# IronDriverInterfaceRevA.net
KiCad netlist of a schematic drawn in EAGLE
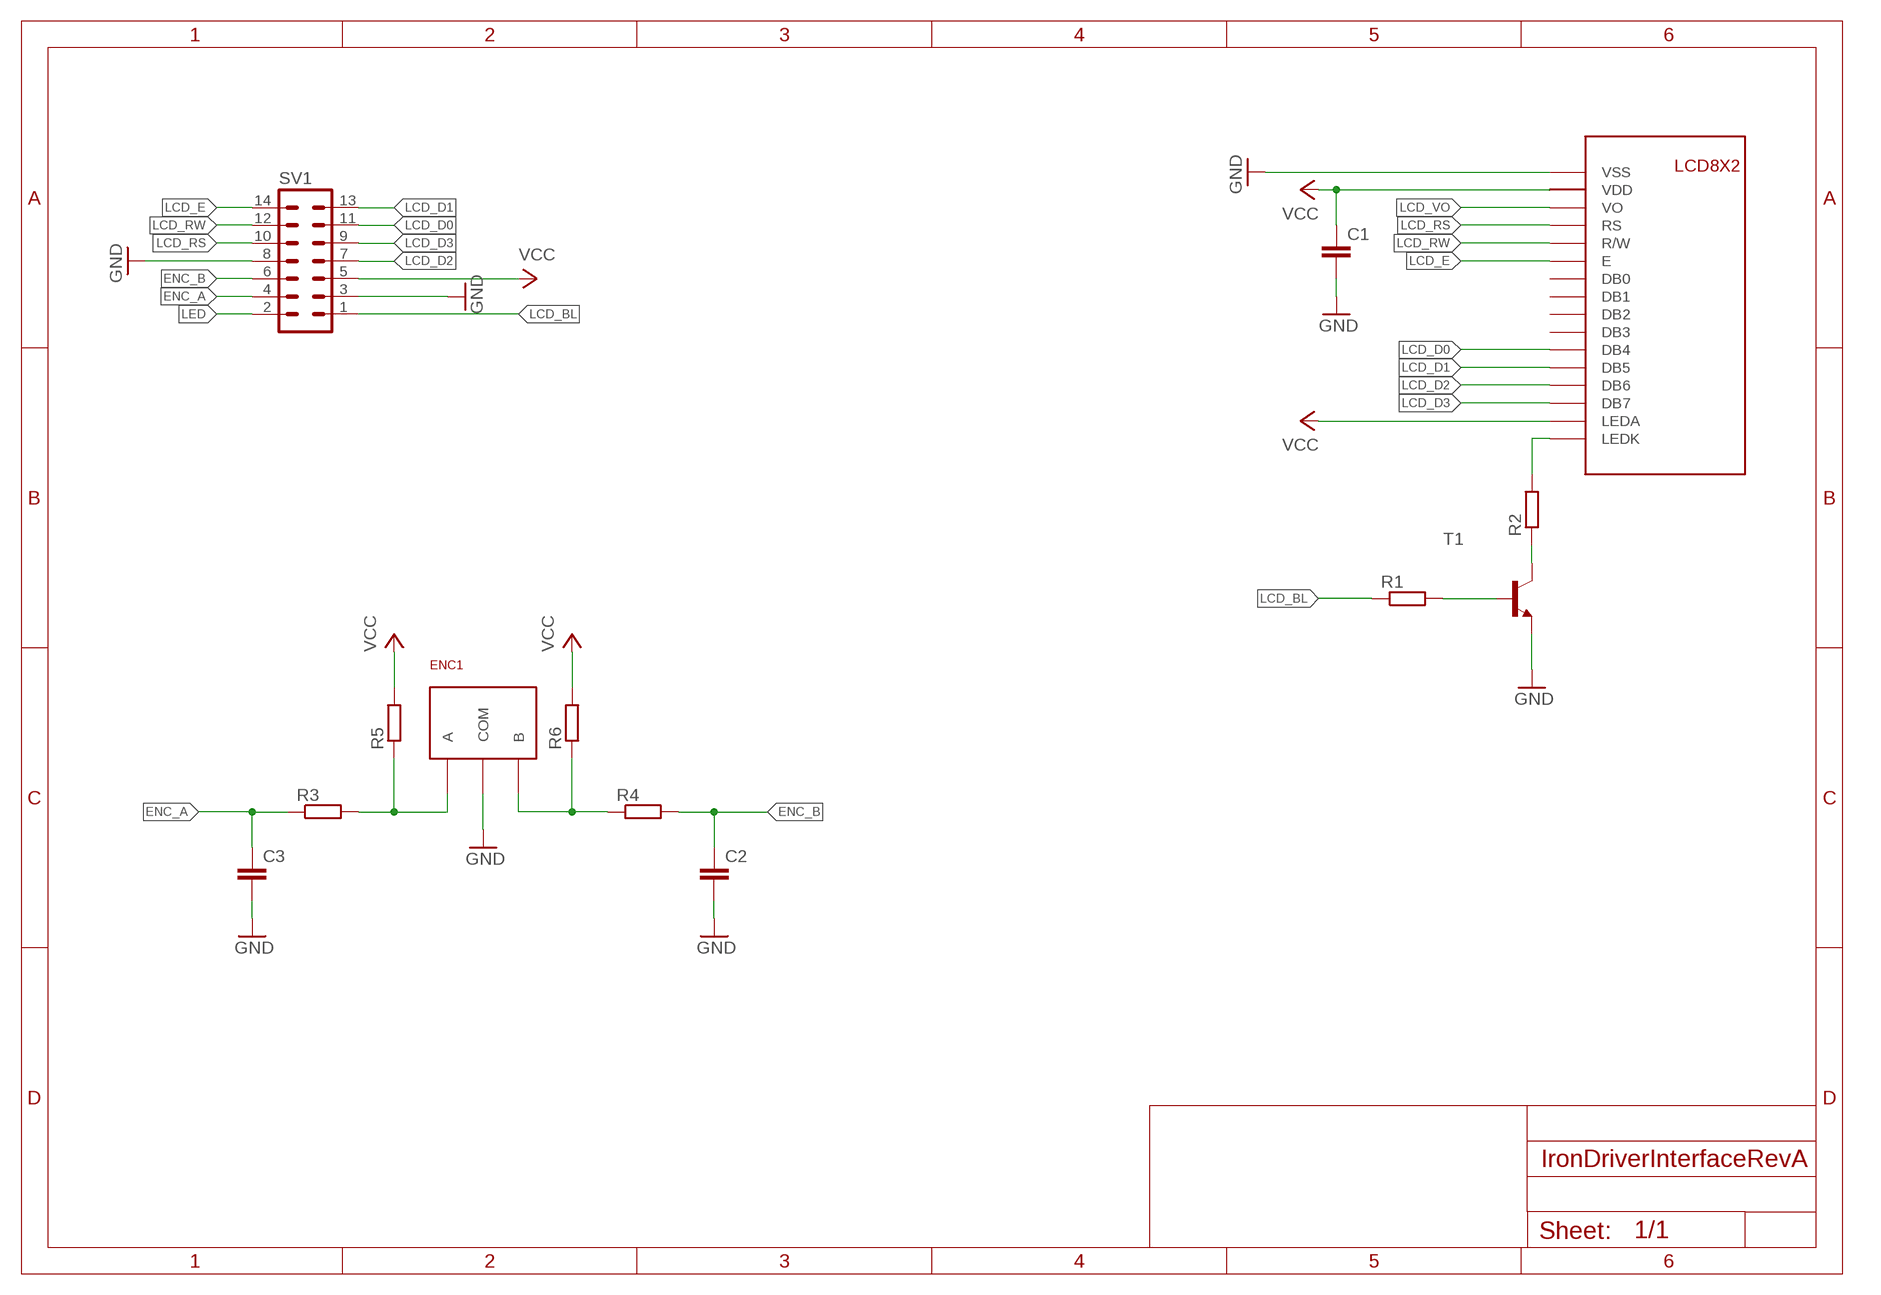
[diagram p0: schematic, sheet 1]

(export (version "E")
  (design (tool "Eeschema 10.0.6"))
  (components
    (comp (ref "C1")
      (value "C-EUC0805")
      (footprint "eagle-import:C0805")
      (libsource (lib "eagle-import") (part "C-EUC0805"))
    )
    (comp (ref "C2")
      (value "C-EUC0805")
      (footprint "eagle-import:C0805")
      (libsource (lib "eagle-import") (part "C-EUC0805"))
    )
    (comp (ref "C3")
      (value "C-EUC0805")
      (footprint "eagle-import:C0805")
      (libsource (lib "eagle-import") (part "C-EUC0805"))
    )
    (comp (ref "ENC1")
      (value "ENCODER")
      (footprint "eagle-import:ENCODER_FOOTPRINT")
      (libsource (lib "eagle-import") (part "ENCODER"))
    )
    (comp (ref "LCD1")
      (value "HC0821")
      (footprint "eagle-import:LCD0821_FOOTPRINT")
      (libsource (lib "eagle-import") (part "HC0821"))
    )
    (comp (ref "R1")
      (value "R-EU_R0805")
      (footprint "eagle-import:R0805")
      (libsource (lib "eagle-import") (part "R-EU_R0805"))
    )
    (comp (ref "R2")
      (value "R-EU_R0805")
      (footprint "eagle-import:R0805")
      (libsource (lib "eagle-import") (part "R-EU_R0805"))
    )
    (comp (ref "R3")
      (value "R-EU_R0805")
      (footprint "eagle-import:R0805")
      (libsource (lib "eagle-import") (part "R-EU_R0805"))
    )
    (comp (ref "R4")
      (value "R-EU_R0805")
      (footprint "eagle-import:R0805")
      (libsource (lib "eagle-import") (part "R-EU_R0805"))
    )
    (comp (ref "R5")
      (value "R-EU_R0805")
      (footprint "eagle-import:R0805")
      (libsource (lib "eagle-import") (part "R-EU_R0805"))
    )
    (comp (ref "R6")
      (value "R-EU_R0805")
      (footprint "eagle-import:R0805")
      (libsource (lib "eagle-import") (part "R-EU_R0805"))
    )
    (comp (ref "SV1")
      (value "MA07-2")
      (footprint "eagle-import:MA07-2")
      (libsource (lib "eagle-import") (part "MA07-2"))
    )
    (comp (ref "T1")
      (value "MMBT3904LT1-NPN-SOT23-BEC")
      (footprint "eagle-import:SOT23-BEC")
      (libsource (lib "eagle-import") (part "-NPN-SOT23-BECMMBT3904LT1"))
    )
  )
  (nets
    (net (code "1") (name "ENC_A") (class "Default")
      (node (ref "C3") (pin "1") (pinfunction "1_1") (pintype "passive"))
      (node (ref "R3") (pin "1") (pinfunction "1_1") (pintype "passive"))
      (node (ref "SV1") (pin "4") (pinfunction "4_4") (pintype "passive"))
    )
    (net (code "2") (name "ENC_B") (class "Default")
      (node (ref "C2") (pin "1") (pinfunction "1_1") (pintype "passive"))
      (node (ref "R4") (pin "2") (pinfunction "2_2") (pintype "passive"))
      (node (ref "SV1") (pin "6") (pinfunction "6_6") (pintype "passive"))
    )
    (net (code "3") (name "GND") (class "Default")
      (node (ref "C1") (pin "2") (pinfunction "2_2") (pintype "passive"))
      (node (ref "C2") (pin "2") (pinfunction "2_2") (pintype "passive"))
      (node (ref "C3") (pin "2") (pinfunction "2_2") (pintype "passive"))
      (node (ref "ENC1") (pin "P$2") (pinfunction "COM_P$2") (pintype "bidirectional"))
      (node (ref "LCD1") (pin "P$1") (pinfunction "VSS_P$1") (pintype "bidirectional"))
      (node (ref "SV1") (pin "3") (pinfunction "3_3") (pintype "passive"))
      (node (ref "SV1") (pin "8") (pinfunction "8_8") (pintype "passive"))
      (node (ref "T1") (pin "E") (pinfunction "E_E") (pintype "passive"))
    )
    (net (code "4") (name "LCD_BL") (class "Default")
      (node (ref "R1") (pin "1") (pinfunction "1_1") (pintype "passive"))
      (node (ref "SV1") (pin "1") (pinfunction "1_1") (pintype "passive"))
    )
    (net (code "5") (name "LCD_D0") (class "Default")
      (node (ref "LCD1") (pin "P$11") (pinfunction "DB4_P$11") (pintype "bidirectional"))
      (node (ref "SV1") (pin "11") (pinfunction "11_11") (pintype "passive"))
    )
    (net (code "6") (name "LCD_D1") (class "Default")
      (node (ref "LCD1") (pin "P$12") (pinfunction "DB5_P$12") (pintype "bidirectional"))
      (node (ref "SV1") (pin "13") (pinfunction "13_13") (pintype "passive"))
    )
    (net (code "7") (name "LCD_D2") (class "Default")
      (node (ref "LCD1") (pin "P$13") (pinfunction "DB6_P$13") (pintype "bidirectional"))
      (node (ref "SV1") (pin "7") (pinfunction "7_7") (pintype "passive"))
    )
    (net (code "8") (name "LCD_D3") (class "Default")
      (node (ref "LCD1") (pin "P$14") (pinfunction "DB7_P$14") (pintype "bidirectional"))
      (node (ref "SV1") (pin "9") (pinfunction "9_9") (pintype "passive"))
    )
    (net (code "9") (name "LCD_E") (class "Default")
      (node (ref "LCD1") (pin "P$6") (pinfunction "E_P$6") (pintype "bidirectional"))
      (node (ref "SV1") (pin "14") (pinfunction "14_14") (pintype "passive"))
    )
    (net (code "10") (name "LCD_RS") (class "Default")
      (node (ref "LCD1") (pin "P$4") (pinfunction "RS_P$4") (pintype "bidirectional"))
      (node (ref "SV1") (pin "10") (pinfunction "10_10") (pintype "passive"))
    )
    (net (code "11") (name "LCD_RW") (class "Default")
      (node (ref "LCD1") (pin "P$5") (pinfunction "R/W_P$5") (pintype "bidirectional"))
      (node (ref "SV1") (pin "12") (pinfunction "12_12") (pintype "passive"))
    )
    (net (code "12") (name "LCD_VO") (class "Default")
      (node (ref "LCD1") (pin "P$3") (pinfunction "VO_P$3") (pintype "bidirectional"))
    )
    (net (code "13") (name "LED") (class "Default")
      (node (ref "SV1") (pin "2") (pinfunction "2_2") (pintype "passive"))
    )
    (net (code "14") (name "Net-(ENC1-A)") (class "Default")
      (node (ref "ENC1") (pin "P$1") (pinfunction "A_P$1") (pintype "bidirectional"))
      (node (ref "R3") (pin "2") (pinfunction "2_2") (pintype "passive"))
      (node (ref "R5") (pin "1") (pinfunction "1_1") (pintype "passive"))
    )
    (net (code "15") (name "Net-(ENC1-B)") (class "Default")
      (node (ref "ENC1") (pin "P$3") (pinfunction "B_P$3") (pintype "bidirectional"))
      (node (ref "R4") (pin "1") (pinfunction "1_1") (pintype "passive"))
      (node (ref "R6") (pin "1") (pinfunction "1_1") (pintype "passive"))
    )
    (net (code "16") (name "Net-(LCD1-LEDK)") (class "Default")
      (node (ref "LCD1") (pin "P$16") (pinfunction "LEDK_P$16") (pintype "bidirectional"))
      (node (ref "R2") (pin "2") (pinfunction "2_2") (pintype "passive"))
    )
    (net (code "17") (name "Net-(R1-Pad2)") (class "Default")
      (node (ref "R1") (pin "2") (pinfunction "2_2") (pintype "passive"))
      (node (ref "T1") (pin "B") (pinfunction "B_B") (pintype "passive"))
    )
    (net (code "18") (name "Net-(R2-Pad1)") (class "Default")
      (node (ref "R2") (pin "1") (pinfunction "1_1") (pintype "passive"))
      (node (ref "T1") (pin "C") (pinfunction "C_C") (pintype "passive"))
    )
    (net (code "19") (name "VCC") (class "Default")
      (node (ref "C1") (pin "1") (pinfunction "1_1") (pintype "passive"))
      (node (ref "LCD1") (pin "P$15") (pinfunction "LEDA_P$15") (pintype "bidirectional"))
      (node (ref "LCD1") (pin "P$2") (pinfunction "VDD_P$2") (pintype "bidirectional"))
      (node (ref "R5") (pin "2") (pinfunction "2_2") (pintype "passive"))
      (node (ref "R6") (pin "2") (pinfunction "2_2") (pintype "passive"))
      (node (ref "SV1") (pin "5") (pinfunction "5_5") (pintype "passive"))
    )
    (net (code "20") (name "unconnected-(LCD1-DB0-PadP$7)") (class "Default")
      (node (ref "LCD1") (pin "P$7") (pinfunction "DB0_P$7") (pintype "bidirectional"))
    )
    (net (code "21") (name "unconnected-(LCD1-DB1-PadP$8)") (class "Default")
      (node (ref "LCD1") (pin "P$8") (pinfunction "DB1_P$8") (pintype "bidirectional"))
    )
    (net (code "22") (name "unconnected-(LCD1-DB2-PadP$9)") (class "Default")
      (node (ref "LCD1") (pin "P$9") (pinfunction "DB2_P$9") (pintype "bidirectional"))
    )
    (net (code "23") (name "unconnected-(LCD1-DB3-PadP$10)") (class "Default")
      (node (ref "LCD1") (pin "P$10") (pinfunction "DB3_P$10") (pintype "bidirectional"))
    )
  )
)
